# 4_jtag_uart.net
KiCad netlist of a schematic drawn in Altium Designer
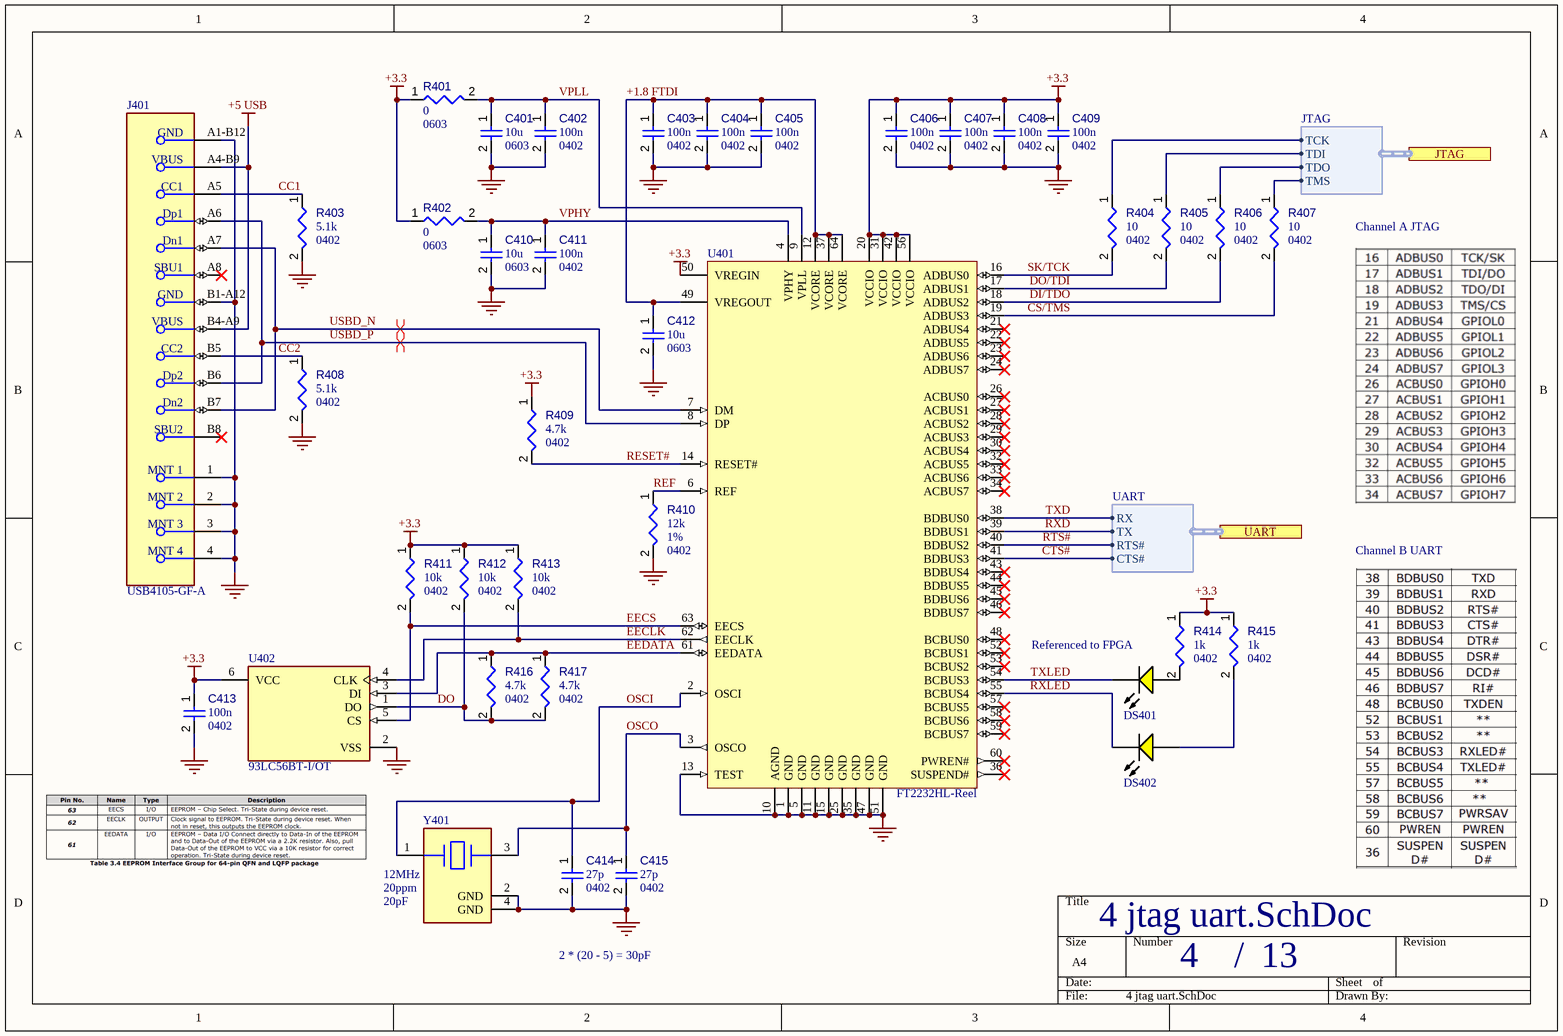
[diagram p0: 4 jtag uart.SchDoc]

(export (version "E")
  (design (tool "Eeschema 10.0.6"))
  (components
    (comp (ref "C401")
      (value "10u")
      (footprint "CAPC0603(1608)100_L")
      (description "Capacitor")
      (fields (field (name "CASE/PACKAGE") "0603") (field (name "Comment") "Capacitors,0603,10u"))
      (libsource (lib "UBC Uncrewed Aircraft Systems") (part "CAP-NP-2"))
    )
    (comp (ref "C402")
      (value "100n")
      (footprint "CAPC0402(1005)60_L")
      (description "Capacitor")
      (fields (field (name "CASE/PACKAGE") "0402") (field (name "Comment") "Capacitors,0402,100n,16"))
      (libsource (lib "UBC Uncrewed Aircraft Systems") (part "CAP-NP-2"))
    )
    (comp (ref "C403")
      (value "100n")
      (footprint "CAPC0402(1005)60_L")
      (description "Capacitor")
      (fields (field (name "CASE/PACKAGE") "0402") (field (name "Comment") "Capacitors,0402,100n,16"))
      (libsource (lib "UBC Uncrewed Aircraft Systems") (part "CAP-NP-2"))
    )
    (comp (ref "C404")
      (value "100n")
      (footprint "CAPC0402(1005)60_L")
      (description "Capacitor")
      (fields (field (name "CASE/PACKAGE") "0402") (field (name "Comment") "Capacitors,0402,100n,16"))
      (libsource (lib "UBC Uncrewed Aircraft Systems") (part "CAP-NP-2"))
    )
    (comp (ref "C405")
      (value "100n")
      (footprint "CAPC0402(1005)60_L")
      (description "Capacitor")
      (fields (field (name "CASE/PACKAGE") "0402") (field (name "Comment") "Capacitors,0402,100n,16"))
      (libsource (lib "UBC Uncrewed Aircraft Systems") (part "CAP-NP-2"))
    )
    (comp (ref "C406")
      (value "100n")
      (footprint "CAPC0402(1005)60_L")
      (description "Capacitor")
      (fields (field (name "CASE/PACKAGE") "0402") (field (name "Comment") "Capacitors,0402,100n,16"))
      (libsource (lib "UBC Uncrewed Aircraft Systems") (part "CAP-NP-2"))
    )
    (comp (ref "C407")
      (value "100n")
      (footprint "CAPC0402(1005)60_L")
      (description "Capacitor")
      (fields (field (name "CASE/PACKAGE") "0402") (field (name "Comment") "Capacitors,0402,100n,16"))
      (libsource (lib "UBC Uncrewed Aircraft Systems") (part "CAP-NP-2"))
    )
    (comp (ref "C408")
      (value "100n")
      (footprint "CAPC0402(1005)60_L")
      (description "Capacitor")
      (fields (field (name "CASE/PACKAGE") "0402") (field (name "Comment") "Capacitors,0402,100n,16"))
      (libsource (lib "UBC Uncrewed Aircraft Systems") (part "CAP-NP-2"))
    )
    (comp (ref "C409")
      (value "100n")
      (footprint "CAPC0402(1005)60_L")
      (description "Capacitor")
      (fields (field (name "CASE/PACKAGE") "0402") (field (name "Comment") "Capacitors,0402,100n,16"))
      (libsource (lib "UBC Uncrewed Aircraft Systems") (part "CAP-NP-2"))
    )
    (comp (ref "C410")
      (value "10u")
      (footprint "CAPC0603(1608)100_L")
      (description "Capacitor")
      (fields (field (name "CASE/PACKAGE") "0603") (field (name "Comment") "Capacitors,0603,10u"))
      (libsource (lib "UBC Uncrewed Aircraft Systems") (part "CAP-NP-2"))
    )
    (comp (ref "C411")
      (value "100n")
      (footprint "CAPC0402(1005)60_L")
      (description "Capacitor")
      (fields (field (name "CASE/PACKAGE") "0402") (field (name "Comment") "Capacitors,0402,100n,16"))
      (libsource (lib "UBC Uncrewed Aircraft Systems") (part "CAP-NP-2"))
    )
    (comp (ref "C412")
      (value "10u")
      (footprint "CAPC0603(1608)100_L")
      (description "Capacitor")
      (fields (field (name "CASE/PACKAGE") "0603") (field (name "Comment") "Capacitors,0603,10u"))
      (libsource (lib "UBC Uncrewed Aircraft Systems") (part "CAP-NP-2"))
    )
    (comp (ref "C413")
      (value "100n")
      (footprint "CAPC0402(1005)60_L")
      (description "Capacitor")
      (fields (field (name "CASE/PACKAGE") "0402") (field (name "Comment") "Capacitors,0402,100n,16"))
      (libsource (lib "UBC Uncrewed Aircraft Systems") (part "CAP-NP-2"))
    )
    (comp (ref "C414")
      (value "27p")
      (footprint "CAPC0402(1005)60_L")
      (description "Capacitor")
      (fields (field (name "CASE/PACKAGE") "0402") (field (name "Comment") "Capacitors,0402,27p"))
      (libsource (lib "UBC Uncrewed Aircraft Systems") (part "CAP-NP-2"))
    )
    (comp (ref "C415")
      (value "27p")
      (footprint "CAPC0402(1005)60_L")
      (description "Capacitor")
      (fields (field (name "CASE/PACKAGE") "0402") (field (name "Comment") "Capacitors,0402,27p"))
      (libsource (lib "UBC Uncrewed Aircraft Systems") (part "CAP-NP-2"))
    )
    (comp (ref "DS401")
      (value "SML-LX0603YW-TR")
      (footprint "LUMX-SML-LX0603_V")
      (fields (field (name "MANUFACTURER") "Lumex"))
      (libsource (lib "Altium Content Vault") (part "LED-YELLOW-AK-2"))
    )
    (comp (ref "DS402")
      (value "SML-LX0603YW-TR")
      (footprint "LUMX-SML-LX0603_V")
      (fields (field (name "MANUFACTURER") "Lumex"))
      (libsource (lib "Altium Content Vault") (part "LED-YELLOW-AK-2"))
    )
    (comp (ref "J401")
      (value "USB4105-GF-A")
      (footprint "FP-USB4105-GF-A-MFG")
      (description "CONN RCPT USB2.0 TYPEC 5A")
      (fields
        (field (name "MANUFACTURER") "GCT")
        (field (name "OCTOPART") "https://octopart.com/usb4105-gf-a-gct-106627878")
      )
      (libsource (lib "Altium Content Vault") (part "e7c17a616881a82b79941196b4bec10"))
    )
    (comp (ref "R401")
      (value "0")
      (footprint "RESC0603(1608)_L")
      (description "Resistor")
      (fields (field (name "CASE/PACKAGE") "0603") (field (name "Comment") "Resistors,0603,0"))
      (libsource (lib "UBC Uncrewed Aircraft Systems") (part "RES-2"))
    )
    (comp (ref "R402")
      (value "0")
      (footprint "RESC0603(1608)_L")
      (description "Resistor")
      (fields (field (name "CASE/PACKAGE") "0603") (field (name "Comment") "Resistors,0603,0"))
      (libsource (lib "UBC Uncrewed Aircraft Systems") (part "RES-2"))
    )
    (comp (ref "R403")
      (value "5.1k")
      (footprint "RESC0402(1005)_L")
      (description "Resistor")
      (fields (field (name "CASE/PACKAGE") "0402") (field (name "Comment") "Resistors,0402,5.1k"))
      (libsource (lib "UBC Uncrewed Aircraft Systems") (part "RES-2"))
    )
    (comp (ref "R404")
      (value "10")
      (footprint "RESC0402(1005)_L")
      (description "Resistor")
      (fields (field (name "CASE/PACKAGE") "0402") (field (name "Comment") "Resistors,0402,10"))
      (libsource (lib "UBC Uncrewed Aircraft Systems") (part "RES-2"))
    )
    (comp (ref "R405")
      (value "10")
      (footprint "RESC0402(1005)_L")
      (description "Resistor")
      (fields (field (name "CASE/PACKAGE") "0402") (field (name "Comment") "Resistors,0402,10"))
      (libsource (lib "UBC Uncrewed Aircraft Systems") (part "RES-2"))
    )
    (comp (ref "R406")
      (value "10")
      (footprint "RESC0402(1005)_L")
      (description "Resistor")
      (fields (field (name "CASE/PACKAGE") "0402") (field (name "Comment") "Resistors,0402,10"))
      (libsource (lib "UBC Uncrewed Aircraft Systems") (part "RES-2"))
    )
    (comp (ref "R407")
      (value "10")
      (footprint "RESC0402(1005)_L")
      (description "Resistor")
      (fields (field (name "CASE/PACKAGE") "0402") (field (name "Comment") "Resistors,0402,10"))
      (libsource (lib "UBC Uncrewed Aircraft Systems") (part "RES-2"))
    )
    (comp (ref "R408")
      (value "5.1k")
      (footprint "RESC0402(1005)_L")
      (description "Resistor")
      (fields (field (name "CASE/PACKAGE") "0402") (field (name "Comment") "Resistors,0402,5.1k"))
      (libsource (lib "UBC Uncrewed Aircraft Systems") (part "RES-2"))
    )
    (comp (ref "R409")
      (value "4.7k")
      (footprint "RESC0402(1005)_L")
      (description "Resistor")
      (fields (field (name "CASE/PACKAGE") "0402") (field (name "Comment") "Resistors,0402,4.7k"))
      (libsource (lib "UBC Uncrewed Aircraft Systems") (part "RES-2"))
    )
    (comp (ref "R410")
      (value "12k")
      (footprint "RESC0402(1005)_L")
      (description "Resistor")
      (fields
        (field (name "CASE/PACKAGE") "0402")
        (field (name "TOLERANCE") "1%")
        (field (name "Comment") "Resistors,0402,1%,12k")
      )
      (libsource (lib "UBC Uncrewed Aircraft Systems") (part "RES-2"))
    )
    (comp (ref "R411")
      (value "10k")
      (footprint "RESC0402(1005)_L")
      (description "Resistor")
      (fields (field (name "CASE/PACKAGE") "0402") (field (name "Comment") "Resistors,0402,10k"))
      (libsource (lib "UBC Uncrewed Aircraft Systems") (part "RES-2"))
    )
    (comp (ref "R412")
      (value "10k")
      (footprint "RESC0402(1005)_L")
      (description "Resistor")
      (fields (field (name "CASE/PACKAGE") "0402") (field (name "Comment") "Resistors,0402,10k"))
      (libsource (lib "UBC Uncrewed Aircraft Systems") (part "RES-2"))
    )
    (comp (ref "R413")
      (value "10k")
      (footprint "RESC0402(1005)_L")
      (description "Resistor")
      (fields (field (name "CASE/PACKAGE") "0402") (field (name "Comment") "Resistors,0402,10k"))
      (libsource (lib "UBC Uncrewed Aircraft Systems") (part "RES-2"))
    )
    (comp (ref "R414")
      (value "1k")
      (footprint "RESC0402(1005)_L")
      (description "Resistor")
      (fields (field (name "CASE/PACKAGE") "0402") (field (name "Comment") "Resistors,0402,1k"))
      (libsource (lib "UBC Uncrewed Aircraft Systems") (part "RES-2"))
    )
    (comp (ref "R415")
      (value "1k")
      (footprint "RESC0402(1005)_L")
      (description "Resistor")
      (fields (field (name "CASE/PACKAGE") "0402") (field (name "Comment") "Resistors,0402,1k"))
      (libsource (lib "UBC Uncrewed Aircraft Systems") (part "RES-2"))
    )
    (comp (ref "R416")
      (value "4.7k")
      (footprint "RESC0402(1005)_L")
      (description "Resistor")
      (fields (field (name "CASE/PACKAGE") "0402") (field (name "Comment") "Resistors,0402,4.7k"))
      (libsource (lib "UBC Uncrewed Aircraft Systems") (part "RES-2"))
    )
    (comp (ref "R417")
      (value "4.7k")
      (footprint "RESC0402(1005)_L")
      (description "Resistor")
      (fields (field (name "CASE/PACKAGE") "0402") (field (name "Comment") "Resistors,0402,4.7k"))
      (libsource (lib "UBC Uncrewed Aircraft Systems") (part "RES-2"))
    )
    (comp (ref "U401")
      (value "FT2232HL-Reel")
      (footprint "LQFP-64_L")
      (description "Dual High Speed USB To Multipurpose UART/FIFO IC, 64-pin LQFP, Tape and Reel")
      (fields (field (name "MANUFACTURER") "FTDI"))
      (libsource (lib "Altium Content Vault") (part "COM-UART-FT2232H-LQFP64"))
    )
    (comp (ref "U402")
      (value "93LC56BT-I/OT")
      (footprint "FP-C04-028-MFG")
      (description "IC EEPROM 2K SPI 2MHZ SOT23-6")
      (libsource (lib "Altium Content Vault") (part "dc1ae428e19de5f6f67d4f5eaa7d586"))
    )
    (comp (ref "Y401")
      (value "NX3225SA-12.000M-STD-CRS-2")
      (footprint "FP-NX3225SA-MFG")
      (fields
        (field (name "FREQUENCY") "12MHz")
        (field (name "FREQUENCY STABILITY") "20ppm")
        (field (name "LOAD CAPACITANCE") "20pF")
      )
      (libsource (lib "Altium Content Vault") (part "48e526d86b7f2615d98721063c72f49"))
    )
  )
  (nets
    (net (code "3") (name "+3.3") (class "Default")
      (node (ref "C406") (pin "1") (pinfunction "1_1") (pintype "passive"))
      (node (ref "C407") (pin "1") (pinfunction "1_1") (pintype "passive"))
      (node (ref "C408") (pin "1") (pinfunction "1_1") (pintype "passive"))
      (node (ref "C409") (pin "1") (pinfunction "1_1") (pintype "passive"))
      (node (ref "C413") (pin "1") (pinfunction "1_1") (pintype "passive"))
      (node (ref "R401") (pin "1") (pinfunction "1_1") (pintype "passive"))
      (node (ref "R402") (pin "1") (pinfunction "1_1") (pintype "passive"))
      (node (ref "R409") (pin "1") (pinfunction "1_1") (pintype "passive"))
      (node (ref "R411") (pin "1") (pinfunction "1_1") (pintype "passive"))
      (node (ref "R412") (pin "1") (pinfunction "1_1") (pintype "passive"))
      (node (ref "R413") (pin "1") (pinfunction "1_1") (pintype "passive"))
      (node (ref "R414") (pin "1") (pinfunction "1_1") (pintype "passive"))
      (node (ref "R415") (pin "1") (pinfunction "1_1") (pintype "passive"))
      (node (ref "U401") (pin "20") (pinfunction "VCCIO_20") (pintype "power_in"))
      (node (ref "U401") (pin "31") (pinfunction "VCCIO_31") (pintype "power_in"))
      (node (ref "U401") (pin "42") (pinfunction "VCCIO_42") (pintype "power_in"))
      (node (ref "U401") (pin "50") (pinfunction "VREGIN_50") (pintype "power_in"))
      (node (ref "U401") (pin "56") (pinfunction "VCCIO_56") (pintype "power_in"))
      (node (ref "U402") (pin "6") (pinfunction "VCC_6") (pintype "power_in"))
    )
    (net (code "4") (name "+5 USB") (class "Default")
      (node (ref "J401") (pin "A4-B9") (pinfunction "VBUS_A4-B9") (pintype "power_in"))
      (node (ref "J401") (pin "B4-A9") (pinfunction "VBUS_B4-A9") (pintype "bidirectional"))
    )
    (net (code "5") (name "/+1.8 FTDI") (class "Default")
      (node (ref "C403") (pin "1") (pinfunction "1_1") (pintype "passive"))
      (node (ref "C404") (pin "1") (pinfunction "1_1") (pintype "passive"))
      (node (ref "C405") (pin "1") (pinfunction "1_1") (pintype "passive"))
      (node (ref "C412") (pin "1") (pinfunction "1_1") (pintype "passive"))
      (node (ref "U401") (pin "12") (pinfunction "VCORE_12") (pintype "power_in"))
      (node (ref "U401") (pin "37") (pinfunction "VCORE_37") (pintype "power_in"))
      (node (ref "U401") (pin "49") (pinfunction "VREGOUT_49") (pintype "power_in"))
      (node (ref "U401") (pin "64") (pinfunction "VCORE_64") (pintype "power_in"))
    )
    (net (code "6") (name "/CC1") (class "Default")
      (node (ref "J401") (pin "A5") (pinfunction "CC1_A5") (pintype "power_in"))
      (node (ref "R403") (pin "1") (pinfunction "1_1") (pintype "passive"))
    )
    (net (code "7") (name "/CC2") (class "Default")
      (node (ref "J401") (pin "B5") (pinfunction "CC2_B5") (pintype "bidirectional"))
      (node (ref "R408") (pin "1") (pinfunction "1_1") (pintype "passive"))
    )
    (net (code "8") (name "/CS{slash}TMS") (class "Default")
      (node (ref "R407") (pin "2") (pinfunction "2_2") (pintype "passive"))
      (node (ref "U401") (pin "19") (pinfunction "ADBUS3_19") (pintype "bidirectional"))
    )
    (net (code "9") (name "/CTS#") (class "Default")
      (node (ref "U401") (pin "41") (pinfunction "BDBUS3_41") (pintype "bidirectional"))
    )
    (net (code "10") (name "/DI{slash}TDO") (class "Default")
      (node (ref "R406") (pin "2") (pinfunction "2_2") (pintype "passive"))
      (node (ref "U401") (pin "18") (pinfunction "ADBUS2_18") (pintype "bidirectional"))
    )
    (net (code "11") (name "/DO") (class "Default")
      (node (ref "R412") (pin "2") (pinfunction "2_2") (pintype "passive"))
      (node (ref "R416") (pin "2") (pinfunction "2_2") (pintype "passive"))
      (node (ref "R417") (pin "2") (pinfunction "2_2") (pintype "passive"))
      (node (ref "U402") (pin "1") (pinfunction "DO_1") (pintype "output"))
    )
    (net (code "12") (name "/DO{slash}TDI") (class "Default")
      (node (ref "R405") (pin "2") (pinfunction "2_2") (pintype "passive"))
      (node (ref "U401") (pin "17") (pinfunction "ADBUS1_17") (pintype "bidirectional"))
    )
    (net (code "13") (name "/EECLK") (class "Default")
      (node (ref "R413") (pin "2") (pinfunction "2_2") (pintype "passive"))
      (node (ref "U401") (pin "62") (pinfunction "EECLK_62") (pintype "output"))
      (node (ref "U402") (pin "4") (pinfunction "CLK_4") (pintype "input"))
    )
    (net (code "14") (name "/EECS") (class "Default")
      (node (ref "R411") (pin "2") (pinfunction "2_2") (pintype "passive"))
      (node (ref "U401") (pin "63") (pinfunction "EECS_63") (pintype "bidirectional"))
      (node (ref "U402") (pin "5") (pinfunction "CS_5") (pintype "input"))
    )
    (net (code "15") (name "/EEDATA") (class "Default")
      (node (ref "R416") (pin "1") (pinfunction "1_1") (pintype "passive"))
      (node (ref "R417") (pin "1") (pinfunction "1_1") (pintype "passive"))
      (node (ref "U401") (pin "61") (pinfunction "EEDATA_61") (pintype "bidirectional"))
      (node (ref "U402") (pin "3") (pinfunction "DI_3") (pintype "input"))
    )
    (net (code "16") (name "/OSCI") (class "Default")
      (node (ref "C414") (pin "1") (pinfunction "1_1") (pintype "passive"))
      (node (ref "U401") (pin "2") (pinfunction "OSCI_2") (pintype "input"))
      (node (ref "Y401") (pin "1") (pinfunction "1_1") (pintype "passive"))
    )
    (net (code "17") (name "/OSCO") (class "Default")
      (node (ref "C415") (pin "1") (pinfunction "1_1") (pintype "passive"))
      (node (ref "U401") (pin "3") (pinfunction "OSCO_3") (pintype "output"))
      (node (ref "Y401") (pin "3") (pinfunction "3_3") (pintype "passive"))
    )
    (net (code "18") (name "/REF") (class "Default")
      (node (ref "R410") (pin "1") (pinfunction "1_1") (pintype "passive"))
      (node (ref "U401") (pin "6") (pinfunction "REF_6") (pintype "input"))
    )
    (net (code "19") (name "/RESET#") (class "Default")
      (node (ref "R409") (pin "2") (pinfunction "2_2") (pintype "passive"))
      (node (ref "U401") (pin "14") (pinfunction "RESET#_14") (pintype "input"))
    )
    (net (code "20") (name "/RTS#") (class "Default")
      (node (ref "U401") (pin "40") (pinfunction "BDBUS2_40") (pintype "bidirectional"))
    )
    (net (code "21") (name "/RXD") (class "Default")
      (node (ref "U401") (pin "39") (pinfunction "BDBUS1_39") (pintype "bidirectional"))
    )
    (net (code "22") (name "/RXLED") (class "Default")
      (node (ref "DS402") (pin "2") (pinfunction "K_2") (pintype "passive"))
      (node (ref "U401") (pin "55") (pinfunction "BCBUS4_55") (pintype "bidirectional"))
    )
    (net (code "23") (name "/SK{slash}TCK") (class "Default")
      (node (ref "R404") (pin "2") (pinfunction "2_2") (pintype "passive"))
      (node (ref "U401") (pin "16") (pinfunction "ADBUS0_16") (pintype "bidirectional"))
    )
    (net (code "24") (name "/TCK") (class "Default")
      (node (ref "R404") (pin "1") (pinfunction "1_1") (pintype "passive"))
    )
    (net (code "25") (name "/TDI") (class "Default")
      (node (ref "R405") (pin "1") (pinfunction "1_1") (pintype "passive"))
    )
    (net (code "26") (name "/TDO") (class "Default")
      (node (ref "R406") (pin "1") (pinfunction "1_1") (pintype "passive"))
    )
    (net (code "27") (name "/TMS") (class "Default")
      (node (ref "R407") (pin "1") (pinfunction "1_1") (pintype "passive"))
    )
    (net (code "28") (name "/TXD") (class "Default")
      (node (ref "U401") (pin "38") (pinfunction "BDBUS0_38") (pintype "bidirectional"))
    )
    (net (code "29") (name "/TXLED") (class "Default")
      (node (ref "DS401") (pin "2") (pinfunction "K_2") (pintype "passive"))
      (node (ref "U401") (pin "54") (pinfunction "BCBUS3_54") (pintype "bidirectional"))
    )
    (net (code "30") (name "/USBD_N") (class "Default")
      (node (ref "J401") (pin "A7") (pinfunction "Dn1_A7") (pintype "bidirectional"))
      (node (ref "J401") (pin "B7") (pinfunction "Dn2_B7") (pintype "bidirectional"))
      (node (ref "U401") (pin "7") (pinfunction "DM_7") (pintype "input"))
    )
    (net (code "31") (name "/USBD_P") (class "Default")
      (node (ref "J401") (pin "A6") (pinfunction "Dp1_A6") (pintype "bidirectional"))
      (node (ref "J401") (pin "B6") (pinfunction "Dp2_B6") (pintype "bidirectional"))
      (node (ref "U401") (pin "8") (pinfunction "DP_8") (pintype "input"))
    )
    (net (code "32") (name "/VPHY") (class "Default")
      (node (ref "C410") (pin "1") (pinfunction "1_1") (pintype "passive"))
      (node (ref "C411") (pin "1") (pinfunction "1_1") (pintype "passive"))
      (node (ref "R402") (pin "2") (pinfunction "2_2") (pintype "passive"))
      (node (ref "U401") (pin "4") (pinfunction "VPHY_4") (pintype "power_in"))
    )
    (net (code "33") (name "/VPLL") (class "Default")
      (node (ref "C401") (pin "1") (pinfunction "1_1") (pintype "passive"))
      (node (ref "C402") (pin "1") (pinfunction "1_1") (pintype "passive"))
      (node (ref "R401") (pin "2") (pinfunction "2_2") (pintype "passive"))
      (node (ref "U401") (pin "9") (pinfunction "VPLL_9") (pintype "power_in"))
    )
    (net (code "36") (name "GND") (class "Default")
      (node (ref "C401") (pin "2") (pinfunction "2_2") (pintype "passive"))
      (node (ref "C402") (pin "2") (pinfunction "2_2") (pintype "passive"))
      (node (ref "C403") (pin "2") (pinfunction "2_2") (pintype "passive"))
      (node (ref "C404") (pin "2") (pinfunction "2_2") (pintype "passive"))
      (node (ref "C405") (pin "2") (pinfunction "2_2") (pintype "passive"))
      (node (ref "C406") (pin "2") (pinfunction "2_2") (pintype "passive"))
      (node (ref "C407") (pin "2") (pinfunction "2_2") (pintype "passive"))
      (node (ref "C408") (pin "2") (pinfunction "2_2") (pintype "passive"))
      (node (ref "C409") (pin "2") (pinfunction "2_2") (pintype "passive"))
      (node (ref "C410") (pin "2") (pinfunction "2_2") (pintype "passive"))
      (node (ref "C411") (pin "2") (pinfunction "2_2") (pintype "passive"))
      (node (ref "C412") (pin "2") (pinfunction "2_2") (pintype "passive"))
      (node (ref "C413") (pin "2") (pinfunction "2_2") (pintype "passive"))
      (node (ref "C414") (pin "2") (pinfunction "2_2") (pintype "passive"))
      (node (ref "C415") (pin "2") (pinfunction "2_2") (pintype "passive"))
      (node (ref "J401") (pin "1") (pinfunction "MNT_1_1") (pintype "power_in"))
      (node (ref "J401") (pin "2") (pinfunction "MNT_2_2") (pintype "power_in"))
      (node (ref "J401") (pin "3") (pinfunction "MNT_3_3") (pintype "power_in"))
      (node (ref "J401") (pin "4") (pinfunction "MNT_4_4") (pintype "power_in"))
      (node (ref "J401") (pin "A1-B12") (pinfunction "GND_A1-B12") (pintype "power_in"))
      (node (ref "J401") (pin "B1-A12") (pinfunction "GND_B1-A12") (pintype "bidirectional"))
      (node (ref "R403") (pin "2") (pinfunction "2_2") (pintype "passive"))
      (node (ref "R408") (pin "2") (pinfunction "2_2") (pintype "passive"))
      (node (ref "R410") (pin "2") (pinfunction "2_2") (pintype "passive"))
      (node (ref "U401") (pin "1") (pinfunction "GND_1") (pintype "power_in"))
      (node (ref "U401") (pin "10") (pinfunction "AGND_10") (pintype "power_in"))
      (node (ref "U401") (pin "11") (pinfunction "GND_11") (pintype "power_in"))
      (node (ref "U401") (pin "13") (pinfunction "TEST_13") (pintype "input"))
      (node (ref "U401") (pin "15") (pinfunction "GND_15") (pintype "power_in"))
      (node (ref "U401") (pin "25") (pinfunction "GND_25") (pintype "power_in"))
      (node (ref "U401") (pin "35") (pinfunction "GND_35") (pintype "power_in"))
      (node (ref "U401") (pin "47") (pinfunction "GND_47") (pintype "power_in"))
      (node (ref "U401") (pin "5") (pinfunction "GND_5") (pintype "power_in"))
      (node (ref "U401") (pin "51") (pinfunction "GND_51") (pintype "power_in"))
      (node (ref "U402") (pin "2") (pinfunction "VSS_2") (pintype "power_in"))
      (node (ref "Y401") (pin "2") (pinfunction "GND_2") (pintype "power_in"))
      (node (ref "Y401") (pin "4") (pinfunction "GND_4") (pintype "power_in"))
    )
    (net (code "37") (name "Net-(DS401-A)") (class "Default")
      (node (ref "DS401") (pin "1") (pinfunction "A_1") (pintype "passive"))
      (node (ref "R414") (pin "2") (pinfunction "2_2") (pintype "passive"))
    )
    (net (code "38") (name "Net-(DS402-A)") (class "Default")
      (node (ref "DS402") (pin "1") (pinfunction "A_1") (pintype "passive"))
      (node (ref "R415") (pin "2") (pinfunction "2_2") (pintype "passive"))
    )
    (net (code "39") (name "unconnected-(J401-SBU1-PadA8)") (class "Default")
      (node (ref "J401") (pin "A8") (pinfunction "SBU1_A8") (pintype "bidirectional+no_connect"))
    )
    (net (code "40") (name "unconnected-(J401-SBU2-PadB8)") (class "Default")
      (node (ref "J401") (pin "B8") (pinfunction "SBU2_B8") (pintype "power_in+no_connect"))
    )
    (net (code "41") (name "unconnected-(U401-ACBUS0-Pad26)") (class "Default")
      (node (ref "U401") (pin "26") (pinfunction "ACBUS0_26") (pintype "bidirectional+no_connect"))
    )
    (net (code "42") (name "unconnected-(U401-ACBUS1-Pad27)") (class "Default")
      (node (ref "U401") (pin "27") (pinfunction "ACBUS1_27") (pintype "bidirectional+no_connect"))
    )
    (net (code "43") (name "unconnected-(U401-ACBUS2-Pad28)") (class "Default")
      (node (ref "U401") (pin "28") (pinfunction "ACBUS2_28") (pintype "bidirectional+no_connect"))
    )
    (net (code "44") (name "unconnected-(U401-ACBUS3-Pad29)") (class "Default")
      (node (ref "U401") (pin "29") (pinfunction "ACBUS3_29") (pintype "bidirectional+no_connect"))
    )
    (net (code "45") (name "unconnected-(U401-ACBUS4-Pad30)") (class "Default")
      (node (ref "U401") (pin "30") (pinfunction "ACBUS4_30") (pintype "bidirectional+no_connect"))
    )
    (net (code "46") (name "unconnected-(U401-ACBUS5-Pad32)") (class "Default")
      (node (ref "U401") (pin "32") (pinfunction "ACBUS5_32") (pintype "bidirectional+no_connect"))
    )
    (net (code "47") (name "unconnected-(U401-ACBUS6-Pad33)") (class "Default")
      (node (ref "U401") (pin "33") (pinfunction "ACBUS6_33") (pintype "bidirectional+no_connect"))
    )
    (net (code "48") (name "unconnected-(U401-ACBUS7-Pad34)") (class "Default")
      (node (ref "U401") (pin "34") (pinfunction "ACBUS7_34") (pintype "bidirectional+no_connect"))
    )
    (net (code "49") (name "unconnected-(U401-ADBUS4-Pad21)") (class "Default")
      (node (ref "U401") (pin "21") (pinfunction "ADBUS4_21") (pintype "bidirectional+no_connect"))
    )
    (net (code "50") (name "unconnected-(U401-ADBUS5-Pad22)") (class "Default")
      (node (ref "U401") (pin "22") (pinfunction "ADBUS5_22") (pintype "bidirectional+no_connect"))
    )
    (net (code "51") (name "unconnected-(U401-ADBUS6-Pad23)") (class "Default")
      (node (ref "U401") (pin "23") (pinfunction "ADBUS6_23") (pintype "bidirectional+no_connect"))
    )
    (net (code "52") (name "unconnected-(U401-ADBUS7-Pad24)") (class "Default")
      (node (ref "U401") (pin "24") (pinfunction "ADBUS7_24") (pintype "bidirectional+no_connect"))
    )
    (net (code "53") (name "unconnected-(U401-BCBUS0-Pad48)") (class "Default")
      (node (ref "U401") (pin "48") (pinfunction "BCBUS0_48") (pintype "bidirectional+no_connect"))
    )
    (net (code "54") (name "unconnected-(U401-BCBUS1-Pad52)") (class "Default")
      (node (ref "U401") (pin "52") (pinfunction "BCBUS1_52") (pintype "bidirectional+no_connect"))
    )
    (net (code "55") (name "unconnected-(U401-BCBUS2-Pad53)") (class "Default")
      (node (ref "U401") (pin "53") (pinfunction "BCBUS2_53") (pintype "bidirectional+no_connect"))
    )
    (net (code "56") (name "unconnected-(U401-BCBUS5-Pad57)") (class "Default")
      (node (ref "U401") (pin "57") (pinfunction "BCBUS5_57") (pintype "bidirectional+no_connect"))
    )
    (net (code "57") (name "unconnected-(U401-BCBUS6-Pad58)") (class "Default")
      (node (ref "U401") (pin "58") (pinfunction "BCBUS6_58") (pintype "bidirectional+no_connect"))
    )
    (net (code "58") (name "unconnected-(U401-BCBUS7-Pad59)") (class "Default")
      (node (ref "U401") (pin "59") (pinfunction "BCBUS7_59") (pintype "bidirectional+no_connect"))
    )
    (net (code "59") (name "unconnected-(U401-BDBUS4-Pad43)") (class "Default")
      (node (ref "U401") (pin "43") (pinfunction "BDBUS4_43") (pintype "bidirectional+no_connect"))
    )
    (net (code "60") (name "unconnected-(U401-BDBUS5-Pad44)") (class "Default")
      (node (ref "U401") (pin "44") (pinfunction "BDBUS5_44") (pintype "bidirectional+no_connect"))
    )
    (net (code "61") (name "unconnected-(U401-BDBUS6-Pad45)") (class "Default")
      (node (ref "U401") (pin "45") (pinfunction "BDBUS6_45") (pintype "bidirectional+no_connect"))
    )
    (net (code "62") (name "unconnected-(U401-BDBUS7-Pad46)") (class "Default")
      (node (ref "U401") (pin "46") (pinfunction "BDBUS7_46") (pintype "bidirectional+no_connect"))
    )
    (net (code "63") (name "unconnected-(U401-PWREN#-Pad60)") (class "Default")
      (node (ref "U401") (pin "60") (pinfunction "PWREN#_60") (pintype "output+no_connect"))
    )
    (net (code "64") (name "unconnected-(U401-SUSPEND#-Pad36)") (class "Default")
      (node (ref "U401") (pin "36") (pinfunction "SUSPEND#_36") (pintype "output+no_connect"))
    )
  )
)
